# MainBoard.net
KiCad netlist of a schematic drawn in Altium Designer
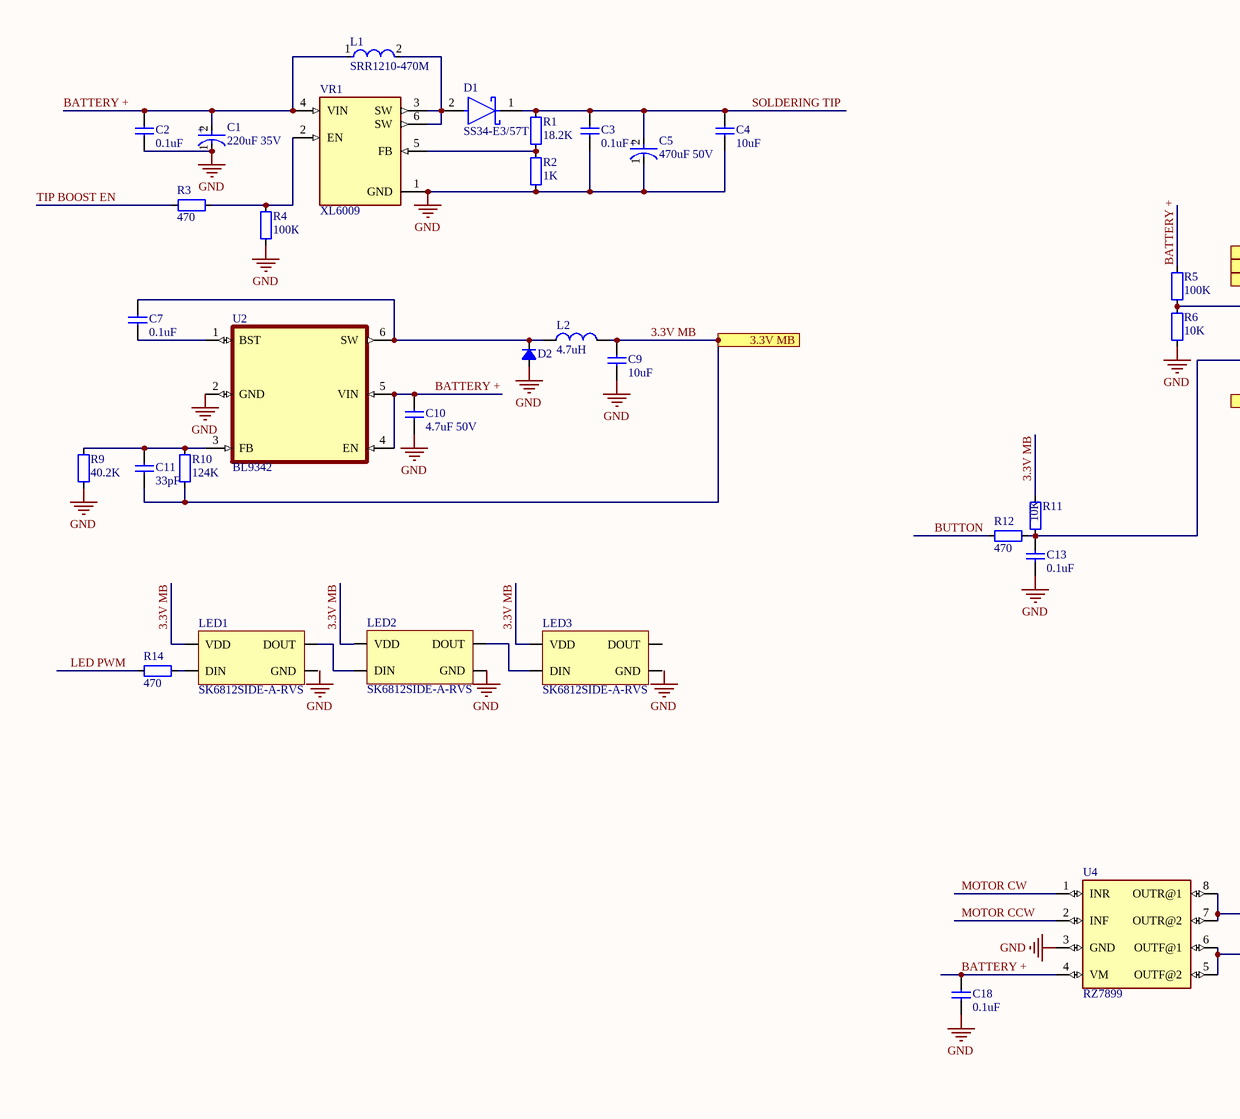
[diagram p0: MainBoard.SchDoc, left]
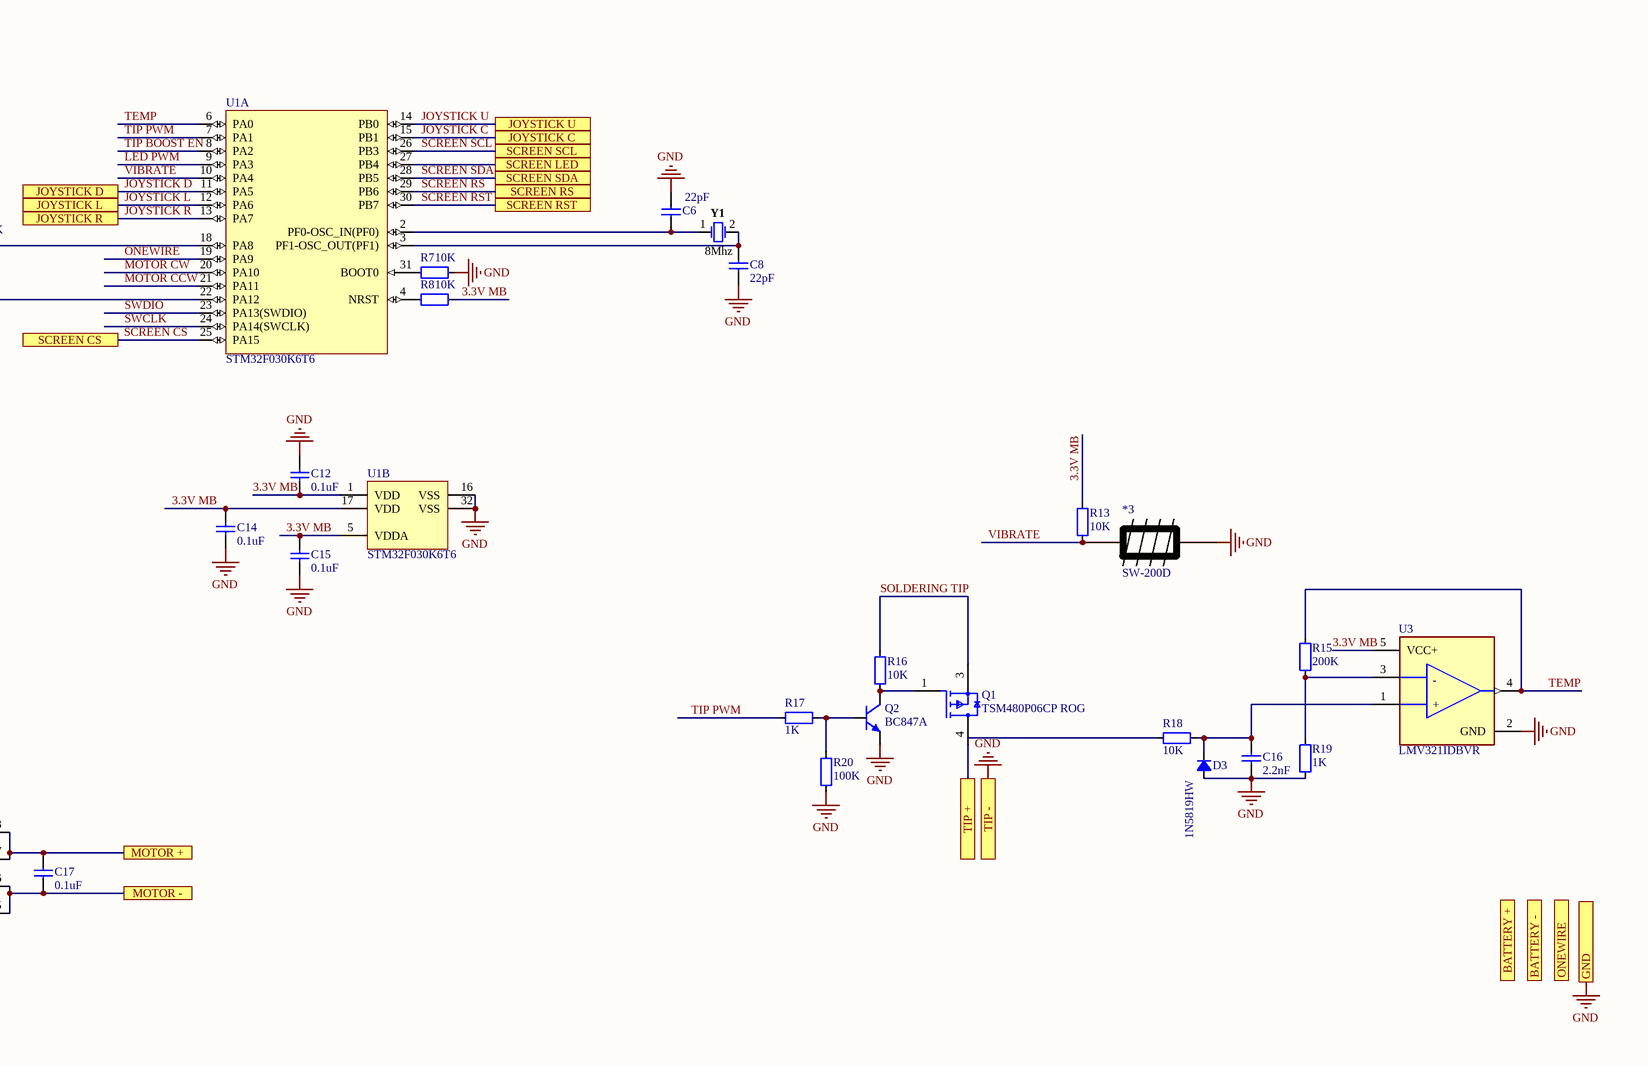
[diagram p1: MainBoard.SchDoc, right]

(export (version "E")
  (design (tool "Eeschema 10.0.6"))
  (components
    (comp (ref "*3")
      (value "SW-200D")
      (footprint "SW-200D")
      (libsource (lib "V_NB-IoT_3.1") (part "SW-200D"))
    )
    (comp (ref "C1")
      (value "220uF 35V")
      (footprint "FP-RAD-TH-D_8_0_5-L_15_1-MFG")
      (description "Aluminum Electrolytic Capacitors (Radial Lead Type) 220uF ±20% 35V")
      (fields (field (name "TOLERANCE") "20%") (field (name "VOLTAGE") "35V"))
      (libsource (lib "V_NB-IoT_3.1") (part "CMP-05427-000678-1"))
    )
    (comp (ref "C2") (value "0.1uF") (footprint "1206") (libsource (lib "V_NB-IoT_3.1") (part "CAP")))
    (comp (ref "C3") (value "0.1uF") (footprint "1206") (libsource (lib "V_NB-IoT_3.1") (part "CAP")))
    (comp (ref "C4") (value "10uF") (footprint "CAPC1005X04L") (libsource (lib "V_NB-IoT_3.1") (part "CAP")))
    (comp (ref "C5")
      (value "470uF 50V")
      (footprint "FP-RAD-TH-D_10_0_5-L_20_2-MFG")
      (description "Aluminum Electrolytic Capacitors (Radial Lead Type) 10uF ±20% 400V")
      (fields (field (name "TOLERANCE") "20%") (field (name "VOLTAGE") "400V"))
      (libsource (lib "V_NB-IoT_3.1") (part "CAP 10x20"))
    )
    (comp (ref "C6") (value "22pF") (footprint "R0603") (libsource (lib "V_NB-IoT_3.1") (part "CAP")))
    (comp (ref "C7") (value "0.1uF") (footprint "C0805") (libsource (lib "V_NB-IoT_3.1") (part "CAP")))
    (comp (ref "C8") (value "22pF") (footprint "R0603") (libsource (lib "V_NB-IoT_3.1") (part "CAP")))
    (comp (ref "C9") (value "10uF") (footprint "C0805") (libsource (lib "V_NB-IoT_3.1") (part "CAP")))
    (comp (ref "C10") (value "4.7uF 50V") (footprint "C0805") (libsource (lib "V_NB-IoT_3.1") (part "CAP")))
    (comp (ref "C11") (value "33pF") (footprint "C0805") (libsource (lib "V_NB-IoT_3.1") (part "CAP")))
    (comp (ref "C12") (value "0.1uF") (footprint "1206") (libsource (lib "V_NB-IoT_3.1") (part "CAP")))
    (comp (ref "C13") (value "0.1uF") (footprint "R0603") (libsource (lib "V_NB-IoT_3.1") (part "CAP")))
    (comp (ref "C14") (value "0.1uF") (footprint "1206") (libsource (lib "V_NB-IoT_3.1") (part "CAP")))
    (comp (ref "C15") (value "0.1uF") (footprint "1206") (libsource (lib "V_NB-IoT_3.1") (part "CAP")))
    (comp (ref "C16") (value "2.2nF") (footprint "C0805") (libsource (lib "V_NB-IoT_3.1") (part "CAP")))
    (comp (ref "C17") (value "0.1uF") (footprint "1206") (libsource (lib "V_NB-IoT_3.1") (part "CAP")))
    (comp (ref "C18") (value "0.1uF") (footprint "1206") (libsource (lib "V_NB-IoT_3.1") (part "CAP")))
    (comp (ref "D1")
      (value "SS34-E3/57T")
      (footprint "FP-95402-MFG")
      (description "DIODE SCHOTTKY 40V 3A DO214AB")
      (fields
        (field (name "MANUFACTURER") "Vishay")
        (field (name "OCTOPART") "https://octopart.com/ss34-e3%2F57t-vishay-39552907")
      )
      (libsource (lib "V_NB-IoT_3.1") (part "SS34"))
    )
    (comp (ref "D2")
      (value "~")
      (footprint "SOD-123")
      (description "Schottky diode SOD123")
      (libsource (lib "V_NB-IoT_3.1") (part "Diode_SOD123"))
    )
    (comp (ref "D3")
      (value "1N5819HW")
      (footprint "SOD-123")
      (description "Schottky diode SOD123 1N5819HW")
      (libsource (lib "V_NB-IoT_3.1") (part "Diode_SOD123"))
    )
    (comp (ref "L1")
      (value "SRR1210-470M")
      (footprint "FP-SRR1210-MFG")
      (description "FIXED IND  102 MOHM SMD")
      (fields (field (name "TOLERANCE") "20%") (field (name "MANUFACTURER") "Bourns"))
      (libsource (lib "V_NB-IoT_3.1") (part "SRR1210"))
    )
    (comp (ref "L2")
      (value "4.7uH")
      (footprint "CDRH3D16NP")
      (description "4,7µH Shielded Inductor 900mA 140mOhm Max Nonstandard")
      (fields
        (field (name "MANUFACTURER") "Sumida")
        (field (name "MANUFACTURER PART NUMBER") "CDRH3D16NP-100NC")
      )
      (libsource (lib "V_NB-IoT_3.1") (part "CDRH3D16NP"))
    )
    (comp (ref "LED1")
      (value "SK6812SIDE-A-RVS")
      (footprint "SK6812SIDE-A-RVS")
      (description "2mA -40℃~+85℃ RGB SMD,2x4mm Light Emitting Diodes (LED) ROHS")
      (libsource (lib "V_NB-IoT_3.1") (part "SK6812SIDE-A-RVS"))
    )
    (comp (ref "LED2")
      (value "SK6812SIDE-A-RVS")
      (footprint "SK6812SIDE-A-RVS")
      (description "2mA -40℃~+85℃ RGB SMD,2x4mm Light Emitting Diodes (LED) ROHS")
      (libsource (lib "V_NB-IoT_3.1") (part "SK6812SIDE-A-RVS"))
    )
    (comp (ref "LED3")
      (value "SK6812SIDE-A-RVS")
      (footprint "SK6812SIDE-A-RVS")
      (description "2mA -40℃~+85℃ RGB SMD,2x4mm Light Emitting Diodes (LED) ROHS")
      (libsource (lib "V_NB-IoT_3.1") (part "SK6812SIDE-A-RVS"))
    )
    (comp (ref "Q1")
      (value "TSM480P06CP ROG")
      (footprint "FP-TO-252-MFG")
      (description "MOSFET P-CHANNEL 60V 20A TO252")
      (libsource (lib "V_NB-IoT_3.1") (part "TSM480P06CP ROG"))
    )
    (comp (ref "Q2")
      (value "BC847A")
      (footprint "SOT95P237X112-3N")
      (description "NPN Silicon AF Transistor, 45 V VCEO, 100 mA IC, SOT23, Reel, Green")
      (fields (field (name "MANUFACTURER") "DIOTEC"))
      (libsource (lib "V_NB-IoT_3.1") (part "BC846A"))
    )
    (comp (ref "R1")
      (value "18.2K")
      (footprint "C0805")
      (description "Resistor SMD")
      (libsource (lib "V_NB-IoT_3.1") (part "RES SMD UNI"))
    )
    (comp (ref "R2")
      (value "1K")
      (footprint "C0805")
      (description "Resistor SMD")
      (libsource (lib "V_NB-IoT_3.1") (part "RES SMD UNI"))
    )
    (comp (ref "R3")
      (value "470")
      (footprint "C0805")
      (description "Resistor SMD")
      (libsource (lib "V_NB-IoT_3.1") (part "RES SMD UNI"))
    )
    (comp (ref "R4")
      (value "100К")
      (footprint "C0805")
      (description "Resistor SMD")
      (libsource (lib "V_NB-IoT_3.1") (part "RES SMD UNI"))
    )
    (comp (ref "R5")
      (value "100K")
      (footprint "C0805")
      (description "Resistor SMD")
      (libsource (lib "V_NB-IoT_3.1") (part "RES SMD UNI"))
    )
    (comp (ref "R6")
      (value "10K")
      (footprint "C0805")
      (description "Resistor SMD")
      (libsource (lib "V_NB-IoT_3.1") (part "RES SMD UNI"))
    )
    (comp (ref "R7")
      (value "10K")
      (footprint "C0805")
      (description "Resistor SMD")
      (libsource (lib "V_NB-IoT_3.1") (part "RES SMD UNI"))
    )
    (comp (ref "R8")
      (value "10K")
      (footprint "C0805")
      (description "Resistor SMD")
      (libsource (lib "V_NB-IoT_3.1") (part "RES SMD UNI"))
    )
    (comp (ref "R9")
      (value "40.2K")
      (footprint "C0805")
      (description "Resistor SMD")
      (libsource (lib "V_NB-IoT_3.1") (part "RES SMD UNI"))
    )
    (comp (ref "R10")
      (value "124K")
      (footprint "C0805")
      (description "Resistor SMD")
      (libsource (lib "V_NB-IoT_3.1") (part "RES SMD UNI"))
    )
    (comp (ref "R11")
      (value "10K")
      (footprint "R0603")
      (description "Resistor SMD")
      (libsource (lib "V_NB-IoT_3.1") (part "RES SMD UNI"))
    )
    (comp (ref "R12")
      (value "470")
      (footprint "R0603")
      (description "Resistor SMD")
      (libsource (lib "V_NB-IoT_3.1") (part "RES SMD UNI"))
    )
    (comp (ref "R13")
      (value "10K")
      (footprint "C0805")
      (description "Resistor SMD")
      (libsource (lib "V_NB-IoT_3.1") (part "RES SMD UNI"))
    )
    (comp (ref "R14")
      (value "470")
      (footprint "C0805")
      (description "Resistor SMD")
      (libsource (lib "V_NB-IoT_3.1") (part "RES SMD UNI"))
    )
    (comp (ref "R15")
      (value "200K")
      (footprint "C0805")
      (description "Resistor SMD")
      (libsource (lib "V_NB-IoT_3.1") (part "RES SMD UNI"))
    )
    (comp (ref "R16")
      (value "10K")
      (footprint "C0805")
      (description "Resistor SMD")
      (libsource (lib "V_NB-IoT_3.1") (part "RES SMD UNI"))
    )
    (comp (ref "R17")
      (value "1K")
      (footprint "C0805")
      (description "Resistor SMD")
      (libsource (lib "V_NB-IoT_3.1") (part "RES SMD UNI"))
    )
    (comp (ref "R18")
      (value "10K")
      (footprint "C0805")
      (description "Resistor SMD")
      (libsource (lib "V_NB-IoT_3.1") (part "RES SMD UNI"))
    )
    (comp (ref "R19")
      (value "1K")
      (footprint "C0805")
      (description "Resistor SMD")
      (libsource (lib "V_NB-IoT_3.1") (part "RES SMD UNI"))
    )
    (comp (ref "R20")
      (value "100K")
      (footprint "C0805")
      (description "Resistor SMD")
      (libsource (lib "V_NB-IoT_3.1") (part "RES SMD UNI"))
    )
    (comp (ref "U1")
      (value "STM32F030K6T6")
      (footprint "LQFP32_L")
      (libsource (lib "V_NB-IoT_3.1") (part "CMP-0304-00020-2"))
    )
    (comp (ref "U2")
      (value "BL9342")
      (footprint "V_NB_IoT_3.1:SOT50P160X60-6N")
      (fields (field (name "MF") "{'manufacturer': u'Texas Instruments'}"))
      (libsource (lib "V_NB-IoT_3.1") (part "BL9342"))
    )
    (comp (ref "U3")
      (value "LMV321IDBVR")
      (footprint "FP-DBV0005A-MFG")
      (description "IC OPAMP GP 1 CIRCUIT SOT23-5")
      (fields
        (field (name "MANUFACTURER") "Texas Instruments")
        (field (name "OCTOPART") "https://octopart.com/lmv321idbvr-texas+instruments-410381")
      )
      (libsource (lib "V_NB-IoT_3.1") (part "LMV321"))
    )
    (comp (ref "U4")
      (value "RZ7899")
      (footprint "SOP-8_2-5R1S-IPC_B")
      (fields (field (name "MF") "{'manufacturer': u'Wuxi'}"))
      (libsource (lib "V_NB-IoT_3.1") (part "RZ7899"))
    )
    (comp (ref "VR1")
      (value "XL6009")
      (footprint "XL6009:DPAK170P1435X465-6N")
      (fields (field (name "MF") "{'manufacturer': u'XLSEMI'}"))
      (libsource (lib "V_NB-IoT_3.1") (part "XL6009"))
    )
    (comp (ref "Y1")
      (value "8Mhz")
      (footprint "FOX-HC49SDLF_V")
      (description "Resistance Weld Crystal, 8 MHz, +/- 30 ppm, -20 to 70 degC, 2-Pin SMD, RoHS, Tape and Reel")
      (fields (field (name "MANUFACTURER") "FOX Electronics") (field (name "TOLERANCE") "50ppm"))
      (libsource (lib "V_NB-IoT_3.1") (part "CMP-2100-03639-1"))
    )
  )
  (nets
    (net (code "1") (name "/3.3V MB") (class "Default")
      (node (ref "C11") (pin "1") (pinfunction "1_1") (pintype "passive"))
      (node (ref "C12") (pin "1") (pinfunction "1_1") (pintype "passive"))
      (node (ref "C14") (pin "1") (pinfunction "1_1") (pintype "passive"))
      (node (ref "C15") (pin "1") (pinfunction "1_1") (pintype "passive"))
      (node (ref "C9") (pin "2") (pinfunction "2_2") (pintype "passive"))
      (node (ref "L2") (pin "2") (pinfunction "2_2") (pintype "passive"))
      (node (ref "LED1") (pin "2") (pinfunction "VDD_2") (pintype "power_in"))
      (node (ref "LED2") (pin "2") (pinfunction "VDD_2") (pintype "power_in"))
      (node (ref "LED3") (pin "2") (pinfunction "VDD_2") (pintype "power_in"))
      (node (ref "R10") (pin "1") (pinfunction "1_1") (pintype "passive"))
      (node (ref "R11") (pin "1") (pinfunction "1_1") (pintype "passive"))
      (node (ref "R13") (pin "2") (pinfunction "2_2") (pintype "passive"))
      (node (ref "R8") (pin "1") (pinfunction "1_1") (pintype "passive"))
      (node (ref "U1") (pin "1") (pinfunction "VDD_1") (pintype "power_in"))
      (node (ref "U1") (pin "17") (pinfunction "VDD_17") (pintype "power_in"))
      (node (ref "U1") (pin "5") (pinfunction "VDDA_5") (pintype "power_in"))
      (node (ref "U3") (pin "5") (pinfunction "VCC+_5") (pintype "power_in"))
    )
    (net (code "2") (name "/BATTERY +") (class "Default")
      (node (ref "C1") (pin "2") (pinfunction "A_2") (pintype "passive"))
      (node (ref "C10") (pin "2") (pinfunction "2_2") (pintype "passive"))
      (node (ref "C18") (pin "1") (pinfunction "1_1") (pintype "passive"))
      (node (ref "C2") (pin "2") (pinfunction "2_2") (pintype "passive"))
      (node (ref "L1") (pin "1") (pinfunction "1_1") (pintype "passive"))
      (node (ref "R5") (pin "2") (pinfunction "2_2") (pintype "passive"))
      (node (ref "U2") (pin "4") (pinfunction "EN_4") (pintype "input"))
      (node (ref "U2") (pin "5") (pinfunction "VIN_5") (pintype "input"))
      (node (ref "U4") (pin "4") (pinfunction "VM_4") (pintype "bidirectional"))
      (node (ref "VR1") (pin "4") (pinfunction "VIN_4") (pintype "input"))
    )
    (net (code "4") (name "/BUTTON") (class "Default")
      (node (ref "R12") (pin "1") (pinfunction "1_1") (pintype "passive"))
    )
    (net (code "5") (name "/JOYSTICK D") (class "Default")
      (node (ref "U1") (pin "11") (pinfunction "PA5_11") (pintype "bidirectional"))
    )
    (net (code "6") (name "/JOYSTICK L") (class "Default")
      (node (ref "U1") (pin "12") (pinfunction "PA6_12") (pintype "bidirectional"))
    )
    (net (code "7") (name "/JOYSTICK R") (class "Default")
      (node (ref "U1") (pin "13") (pinfunction "PA7_13") (pintype "bidirectional"))
    )
    (net (code "8") (name "/JOYSTICK U") (class "Default")
      (node (ref "U1") (pin "14") (pinfunction "PB0_14") (pintype "bidirectional"))
    )
    (net (code "9") (name "/JOYSTICK С") (class "Default")
      (node (ref "U1") (pin "15") (pinfunction "PB1_15") (pintype "bidirectional"))
    )
    (net (code "10") (name "/LED PWM") (class "Default")
      (node (ref "R14") (pin "2") (pinfunction "2_2") (pintype "passive"))
      (node (ref "U1") (pin "9") (pinfunction "PA3_9") (pintype "bidirectional"))
    )
    (net (code "11") (name "/MOTOR +") (class "Default")
      (node (ref "C17") (pin "1") (pinfunction "1_1") (pintype "passive"))
      (node (ref "U4") (pin "7") (pinfunction "OUTR@2_7") (pintype "bidirectional"))
      (node (ref "U4") (pin "8") (pinfunction "OUTR@1_8") (pintype "bidirectional"))
    )
    (net (code "12") (name "/MOTOR -") (class "Default")
      (node (ref "C17") (pin "2") (pinfunction "2_2") (pintype "passive"))
      (node (ref "U4") (pin "5") (pinfunction "OUTF@2_5") (pintype "bidirectional"))
      (node (ref "U4") (pin "6") (pinfunction "OUTF@1_6") (pintype "bidirectional"))
    )
    (net (code "13") (name "/MOTOR CCW") (class "Default")
      (node (ref "U1") (pin "21") (pinfunction "PA11_21") (pintype "bidirectional"))
      (node (ref "U4") (pin "2") (pinfunction "INF_2") (pintype "bidirectional"))
    )
    (net (code "14") (name "/MOTOR CW") (class "Default")
      (node (ref "U1") (pin "20") (pinfunction "PA10_20") (pintype "bidirectional"))
      (node (ref "U4") (pin "1") (pinfunction "INR_1") (pintype "bidirectional"))
    )
    (net (code "15") (name "/ONEWIRE") (class "Default")
      (node (ref "U1") (pin "19") (pinfunction "PA9_19") (pintype "bidirectional"))
    )
    (net (code "16") (name "/SCREEN CS") (class "Default")
      (node (ref "U1") (pin "25") (pinfunction "PA15_25") (pintype "bidirectional"))
    )
    (net (code "17") (name "/SCREEN LED") (class "Default")
      (node (ref "U1") (pin "27") (pinfunction "PB4_27") (pintype "bidirectional"))
    )
    (net (code "18") (name "/SCREEN RS") (class "Default")
      (node (ref "U1") (pin "29") (pinfunction "PB6_29") (pintype "bidirectional"))
    )
    (net (code "19") (name "/SCREEN RST") (class "Default")
      (node (ref "U1") (pin "30") (pinfunction "PB7_30") (pintype "bidirectional"))
    )
    (net (code "20") (name "/SCREEN SCL") (class "Default")
      (node (ref "U1") (pin "26") (pinfunction "PB3_26") (pintype "bidirectional"))
    )
    (net (code "21") (name "/SCREEN SDA") (class "Default")
      (node (ref "U1") (pin "28") (pinfunction "PB5_28") (pintype "bidirectional"))
    )
    (net (code "22") (name "/SOLDERING TIP") (class "Default")
      (node (ref "C3") (pin "2") (pinfunction "2_2") (pintype "passive"))
      (node (ref "C4") (pin "2") (pinfunction "2_2") (pintype "passive"))
      (node (ref "C5") (pin "2") (pinfunction "A_2") (pintype "passive"))
      (node (ref "D1") (pin "1") (pinfunction "C_1") (pintype "passive"))
      (node (ref "Q1") (pin "3") (pinfunction "Source_3") (pintype "passive"))
      (node (ref "R1") (pin "1") (pinfunction "1_1") (pintype "passive"))
      (node (ref "R16") (pin "2") (pinfunction "2_2") (pintype "passive"))
    )
    (net (code "23") (name "/SWCLK") (class "Default")
      (node (ref "U1") (pin "24") (pinfunction "PA14(SWCLK)_24") (pintype "bidirectional"))
    )
    (net (code "24") (name "/SWDIO") (class "Default")
      (node (ref "U1") (pin "23") (pinfunction "PA13(SWDIO)_23") (pintype "bidirectional"))
    )
    (net (code "25") (name "/TEMP") (class "Default")
      (node (ref "R15") (pin "1") (pinfunction "1_1") (pintype "passive"))
      (node (ref "U1") (pin "6") (pinfunction "PA0_6") (pintype "bidirectional"))
      (node (ref "U3") (pin "4") (pinfunction "OUT_4") (pintype "output"))
    )
    (net (code "26") (name "/TIP +") (class "Default")
      (node (ref "Q1") (pin "4") (pinfunction "Drain_4") (pintype "passive"))
    )
    (net (code "27") (name "/TIP BOOST EN") (class "Default")
      (node (ref "R3") (pin "2") (pinfunction "2_2") (pintype "passive"))
      (node (ref "U1") (pin "8") (pinfunction "PA2_8") (pintype "bidirectional"))
    )
    (net (code "28") (name "/TIP PWM") (class "Default")
      (node (ref "R17") (pin "2") (pinfunction "2_2") (pintype "passive"))
      (node (ref "U1") (pin "7") (pinfunction "PA1_7") (pintype "bidirectional"))
    )
    (net (code "29") (name "/VIBRATE") (class "Default")
      (node (ref "*3") (pin "1") (pinfunction "1_1") (pintype "passive"))
      (node (ref "R13") (pin "1") (pinfunction "1_1") (pintype "passive"))
      (node (ref "U1") (pin "10") (pinfunction "PA4_10") (pintype "bidirectional"))
    )
    (net (code "30") (name "GND") (class "Default")
      (node (ref "*3") (pin "2") (pinfunction "2_2") (pintype "passive"))
      (node (ref "C1") (pin "1") (pinfunction "C_1") (pintype "passive"))
      (node (ref "C10") (pin "1") (pinfunction "1_1") (pintype "passive"))
      (node (ref "C12") (pin "2") (pinfunction "2_2") (pintype "passive"))
      (node (ref "C13") (pin "1") (pinfunction "1_1") (pintype "passive"))
      (node (ref "C14") (pin "2") (pinfunction "2_2") (pintype "passive"))
      (node (ref "C15") (pin "2") (pinfunction "2_2") (pintype "passive"))
      (node (ref "C16") (pin "1") (pinfunction "1_1") (pintype "passive"))
      (node (ref "C18") (pin "2") (pinfunction "2_2") (pintype "passive"))
      (node (ref "C2") (pin "1") (pinfunction "1_1") (pintype "passive"))
      (node (ref "C3") (pin "1") (pinfunction "1_1") (pintype "passive"))
      (node (ref "C4") (pin "1") (pinfunction "1_1") (pintype "passive"))
      (node (ref "C5") (pin "1") (pinfunction "C_1") (pintype "passive"))
      (node (ref "C6") (pin "1") (pinfunction "1_1") (pintype "passive"))
      (node (ref "C8") (pin "1") (pinfunction "1_1") (pintype "passive"))
      (node (ref "C9") (pin "1") (pinfunction "1_1") (pintype "passive"))
      (node (ref "D2") (pin "1") (pinfunction "A_1") (pintype "passive"))
      (node (ref "D3") (pin "1") (pinfunction "A_1") (pintype "passive"))
      (node (ref "LED2") (pin "4") (pinfunction "GND_4") (pintype "power_in"))
      (node (ref "Q2") (pin "2") (pinfunction "E_2") (pintype "passive"))
      (node (ref "R19") (pin "2") (pinfunction "2_2") (pintype "passive"))
      (node (ref "R2") (pin "2") (pinfunction "2_2") (pintype "passive"))
      (node (ref "R20") (pin "1") (pinfunction "1_1") (pintype "passive"))
      (node (ref "R4") (pin "2") (pinfunction "2_2") (pintype "passive"))
      (node (ref "R6") (pin "1") (pinfunction "1_1") (pintype "passive"))
      (node (ref "R7") (pin "1") (pinfunction "1_1") (pintype "passive"))
      (node (ref "R9") (pin "1") (pinfunction "1_1") (pintype "passive"))
      (node (ref "U1") (pin "16") (pinfunction "VSS_16") (pintype "power_in"))
      (node (ref "U1") (pin "32") (pinfunction "VSS_32") (pintype "power_in"))
      (node (ref "U2") (pin "2") (pinfunction "GND_2") (pintype "bidirectional"))
      (node (ref "U3") (pin "2") (pinfunction "GND_2") (pintype "power_in"))
      (node (ref "U4") (pin "3") (pinfunction "GND_3") (pintype "bidirectional"))
      (node (ref "VR1") (pin "1") (pinfunction "GND_1") (pintype "power_in"))
    )
    (net (code "31") (name "Net-(D1-A)") (class "Default")
      (node (ref "D1") (pin "2") (pinfunction "A_2") (pintype "passive"))
      (node (ref "L1") (pin "2") (pinfunction "2_2") (pintype "passive"))
      (node (ref "VR1") (pin "3") (pinfunction "SW_3") (pintype "output"))
      (node (ref "VR1") (pin "6") (pinfunction "SW_6") (pintype "output"))
    )
    (net (code "32") (name "Net-(D2-K)") (class "Default")
      (node (ref "C7") (pin "2") (pinfunction "2_2") (pintype "passive"))
      (node (ref "D2") (pin "2") (pinfunction "K_2") (pintype "passive"))
      (node (ref "L2") (pin "1") (pinfunction "1_1") (pintype "passive"))
      (node (ref "U2") (pin "6") (pinfunction "SW_6") (pintype "output"))
    )
    (net (code "33") (name "Net-(D3-K)") (class "Default")
      (node (ref "C16") (pin "2") (pinfunction "2_2") (pintype "passive"))
      (node (ref "D3") (pin "2") (pinfunction "K_2") (pintype "passive"))
      (node (ref "R18") (pin "2") (pinfunction "2_2") (pintype "passive"))
      (node (ref "U3") (pin "1") (pinfunction "1IN+_1") (pintype "tri_state"))
    )
    (net (code "34") (name "Net-(LED1-DIN)") (class "Default")
      (node (ref "LED1") (pin "1") (pinfunction "DIN_1") (pintype "power_in"))
      (node (ref "R14") (pin "1") (pinfunction "1_1") (pintype "passive"))
    )
    (net (code "35") (name "Net-(LED1-DOUT)") (class "Default")
      (node (ref "LED1") (pin "3") (pinfunction "DOUT_3") (pintype "power_in"))
      (node (ref "LED2") (pin "1") (pinfunction "DIN_1") (pintype "power_in"))
    )
    (net (code "36") (name "Net-(LED2-DOUT)") (class "Default")
      (node (ref "LED2") (pin "3") (pinfunction "DOUT_3") (pintype "power_in"))
      (node (ref "LED3") (pin "1") (pinfunction "DIN_1") (pintype "power_in"))
    )
    (net (code "37") (name "Net-(Q1-Gate)") (class "Default")
      (node (ref "Q1") (pin "1") (pinfunction "Gate_1") (pintype "passive"))
      (node (ref "Q2") (pin "3") (pinfunction "C_3") (pintype "passive"))
      (node (ref "R16") (pin "1") (pinfunction "1_1") (pintype "passive"))
    )
    (net (code "38") (name "Net-(Q2-B)") (class "Default")
      (node (ref "Q2") (pin "1") (pinfunction "B_1") (pintype "passive"))
      (node (ref "R17") (pin "1") (pinfunction "1_1") (pintype "passive"))
      (node (ref "R20") (pin "2") (pinfunction "2_2") (pintype "passive"))
    )
    (net (code "39") (name "Net-(U1A-BOOT0)") (class "Default")
      (node (ref "R7") (pin "2") (pinfunction "2_2") (pintype "passive"))
      (node (ref "U1") (pin "31") (pinfunction "BOOT0_31") (pintype "input"))
    )
    (net (code "40") (name "Net-(U1A-NRST)") (class "Default")
      (node (ref "R8") (pin "2") (pinfunction "2_2") (pintype "passive"))
      (node (ref "U1") (pin "4") (pinfunction "NRST_4") (pintype "bidirectional"))
    )
    (net (code "41") (name "Net-(U1A-PA8)") (class "Default")
      (node (ref "R5") (pin "1") (pinfunction "1_1") (pintype "passive"))
      (node (ref "R6") (pin "2") (pinfunction "2_2") (pintype "passive"))
      (node (ref "U1") (pin "18") (pinfunction "PA8_18") (pintype "bidirectional"))
    )
    (net (code "42") (name "Net-(U1A-PA12)") (class "Default")
      (node (ref "C13") (pin "2") (pinfunction "2_2") (pintype "passive"))
      (node (ref "R11") (pin "2") (pinfunction "2_2") (pintype "passive"))
      (node (ref "R12") (pin "2") (pinfunction "2_2") (pintype "passive"))
      (node (ref "U1") (pin "22") (pinfunction "PA12_22") (pintype "bidirectional"))
    )
    (net (code "43") (name "Net-(U1A-PF0-OSC_IN(PF0))") (class "Default")
      (node (ref "C6") (pin "2") (pinfunction "2_2") (pintype "passive"))
      (node (ref "U1") (pin "2") (pinfunction "PF0-OSC_IN(PF0)_2") (pintype "bidirectional"))
      (node (ref "Y1") (pin "1") (pinfunction "1_1") (pintype "passive"))
    )
    (net (code "44") (name "Net-(U1A-PF1-OSC_OUT(PF1))") (class "Default")
      (node (ref "C8") (pin "2") (pinfunction "2_2") (pintype "passive"))
      (node (ref "U1") (pin "3") (pinfunction "PF1-OSC_OUT(PF1)_3") (pintype "bidirectional"))
      (node (ref "Y1") (pin "2") (pinfunction "2_2") (pintype "passive"))
    )
    (net (code "45") (name "Net-(U2-BST)") (class "Default")
      (node (ref "C7") (pin "1") (pinfunction "1_1") (pintype "passive"))
      (node (ref "U2") (pin "1") (pinfunction "BST_1") (pintype "bidirectional"))
    )
    (net (code "46") (name "Net-(U2-FB)") (class "Default")
      (node (ref "C11") (pin "2") (pinfunction "2_2") (pintype "passive"))
      (node (ref "R10") (pin "2") (pinfunction "2_2") (pintype "passive"))
      (node (ref "R9") (pin "2") (pinfunction "2_2") (pintype "passive"))
      (node (ref "U2") (pin "3") (pinfunction "FB_3") (pintype "input"))
    )
    (net (code "47") (name "Net-(U3-1IN-)") (class "Default")
      (node (ref "R15") (pin "2") (pinfunction "2_2") (pintype "passive"))
      (node (ref "R19") (pin "1") (pinfunction "1_1") (pintype "passive"))
      (node (ref "U3") (pin "3") (pinfunction "1IN-_3") (pintype "tri_state"))
    )
    (net (code "48") (name "Net-(VR1-EN)") (class "Default")
      (node (ref "R3") (pin "1") (pinfunction "1_1") (pintype "passive"))
      (node (ref "R4") (pin "1") (pinfunction "1_1") (pintype "passive"))
      (node (ref "VR1") (pin "2") (pinfunction "EN_2") (pintype "input"))
    )
    (net (code "49") (name "Net-(VR1-FB)") (class "Default")
      (node (ref "R1") (pin "2") (pinfunction "2_2") (pintype "passive"))
      (node (ref "R2") (pin "1") (pinfunction "1_1") (pintype "passive"))
      (node (ref "VR1") (pin "5") (pinfunction "FB_5") (pintype "input"))
    )
    (net (code "50") (name "unconnected-(LED1-GND-Pad4)") (class "Default")
      (node (ref "LED1") (pin "4") (pinfunction "GND_4") (pintype "power_in"))
    )
    (net (code "51") (name "unconnected-(LED3-DOUT-Pad3)") (class "Default")
      (node (ref "LED3") (pin "3") (pinfunction "DOUT_3") (pintype "power_in"))
    )
    (net (code "52") (name "unconnected-(LED3-GND-Pad4)") (class "Default")
      (node (ref "LED3") (pin "4") (pinfunction "GND_4") (pintype "power_in"))
    )
    (net (code "53") (name "unconnected-(R18-Pad1)") (class "Default")
      (node (ref "R18") (pin "1") (pinfunction "1_1") (pintype "passive"))
    )
  )
)
